# speedometer.net
KiCad netlist of a schematic drawn in EAGLE
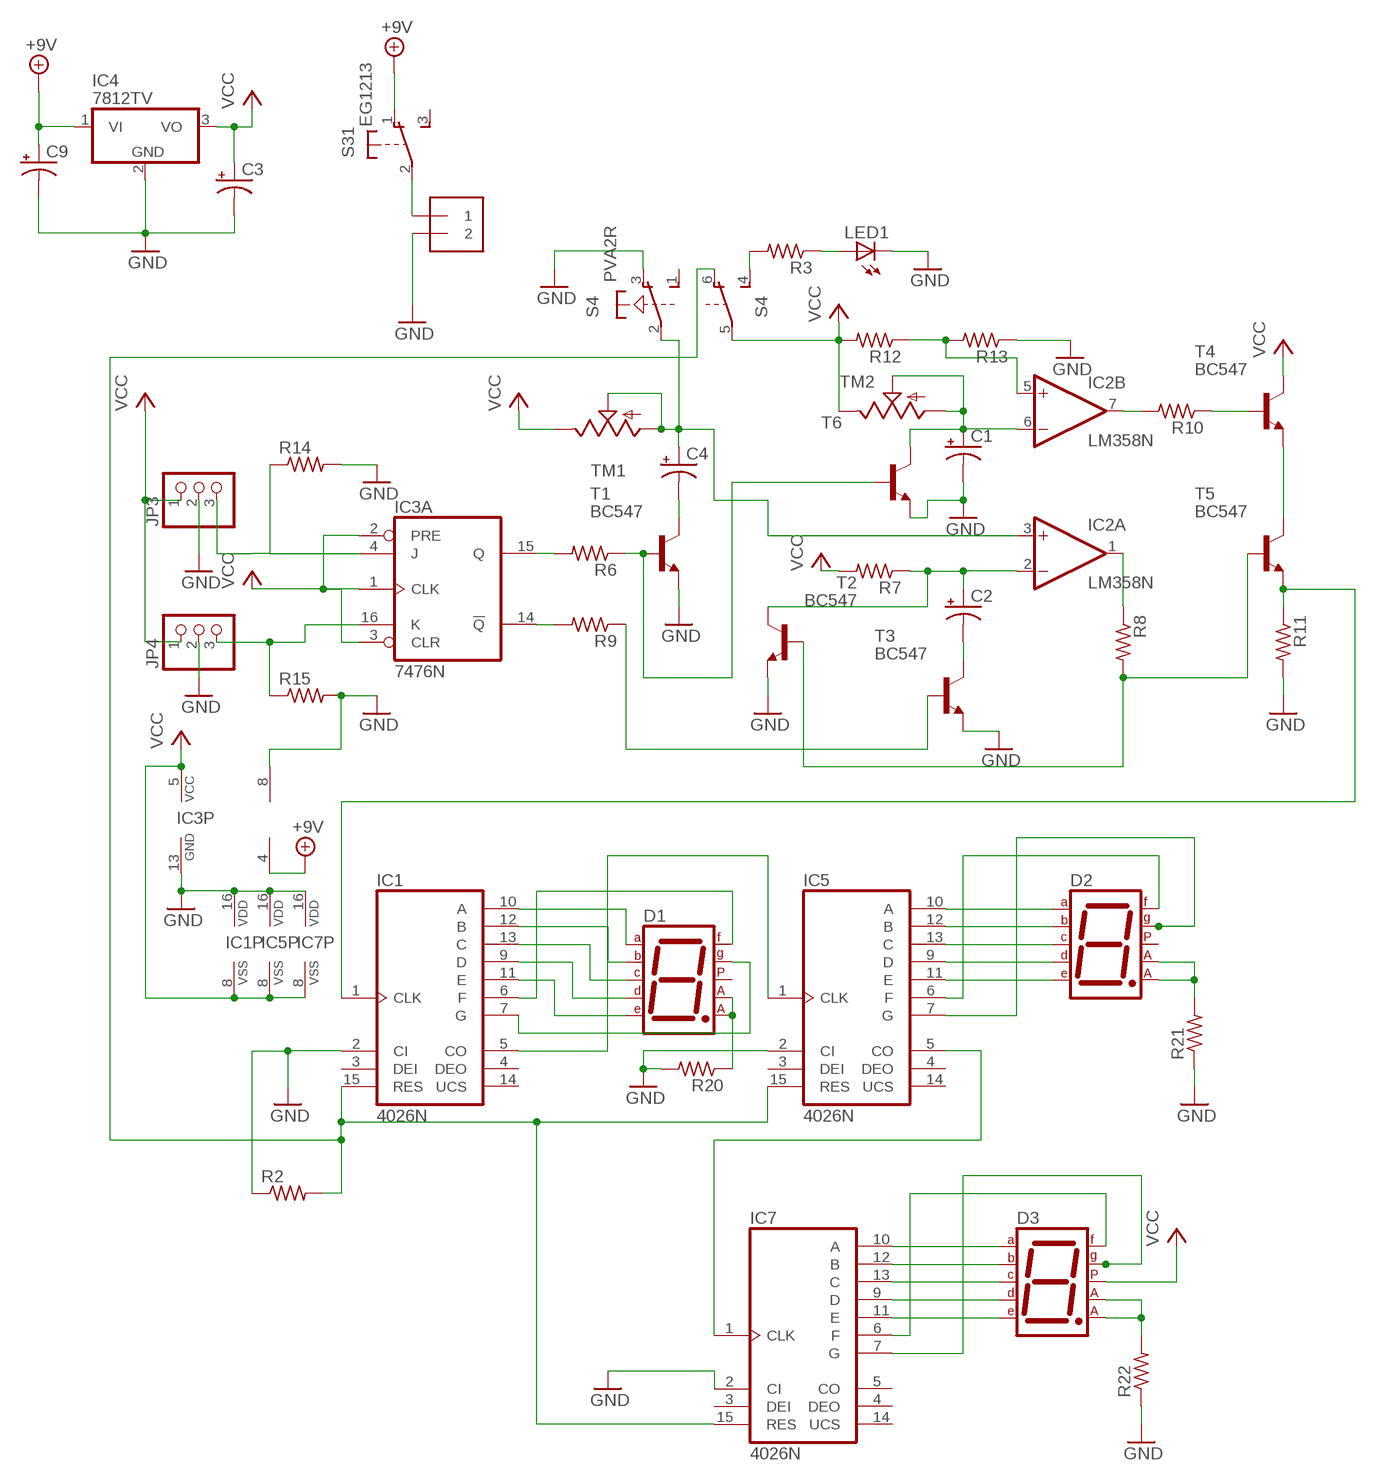
[diagram p0: schematic, sheet 1]

(export (version "E")
  (design (tool "Eeschema 10.0.6"))
  (components
    (comp (ref "C1")
      (value "CPOL-USE2-4")
      (footprint "eagle-import:E2-4")
      (libsource (lib "eagle-import") (part "CPOL-USE2-4"))
    )
    (comp (ref "C2")
      (value "CPOL-USE2-4")
      (footprint "eagle-import:E2-4")
      (libsource (lib "eagle-import") (part "CPOL-USE2-4"))
    )
    (comp (ref "C3")
      (value "CPOL-USE2-4")
      (footprint "eagle-import:E2-4")
      (libsource (lib "eagle-import") (part "CPOL-USE2-4"))
    )
    (comp (ref "C4")
      (value "CPOL-USE2-4")
      (footprint "eagle-import:E2-4")
      (libsource (lib "eagle-import") (part "CPOL-USE2-4"))
    )
    (comp (ref "C9")
      (value "CPOL-USE2.5-6")
      (footprint "eagle-import:E2,5-6")
      (libsource (lib "eagle-import") (part "CPOL-USE2.5-6"))
    )
    (comp (ref "D1")
      (value "7SEG-CA")
      (footprint "eagle-import:7SEG-13")
      (libsource (lib "eagle-import") (part "7SEG-CA"))
    )
    (comp (ref "D2")
      (value "7SEG-CA")
      (footprint "eagle-import:7SEG-13")
      (libsource (lib "eagle-import") (part "7SEG-CA"))
    )
    (comp (ref "D3")
      (value "7SEG-CA")
      (footprint "eagle-import:7SEG-13")
      (libsource (lib "eagle-import") (part "7SEG-CA"))
    )
    (comp (ref "IC1")
      (value "4026N")
      (footprint "eagle-import:DIL16")
      (libsource (lib "eagle-import") (part "4026N"))
    )
    (comp (ref "IC2")
      (value "LM358N")
      (footprint "eagle-import:DIL08")
      (libsource (lib "eagle-import") (part "LM358N"))
    )
    (comp (ref "IC3")
      (value "7476N")
      (footprint "eagle-import:DIL16")
      (libsource (lib "eagle-import") (part "7476N"))
    )
    (comp (ref "IC4")
      (value "7812TV")
      (footprint "eagle-import:TO220V")
      (libsource (lib "eagle-import") (part "78TV12"))
    )
    (comp (ref "IC5")
      (value "4026N")
      (footprint "eagle-import:DIL16")
      (libsource (lib "eagle-import") (part "4026N"))
    )
    (comp (ref "IC7")
      (value "4026N")
      (footprint "eagle-import:DIL16")
      (libsource (lib "eagle-import") (part "4026N"))
    )
    (comp (ref "J1")
      (value "1X2-3.5MM")
      (footprint "eagle-import:1X2-3.5MM")
      (libsource (lib "eagle-import") (part "1X2-3.5MM"))
    )
    (comp (ref "JP3")
      (value "PINHD-1X3")
      (footprint "eagle-import:1X03")
      (libsource (lib "eagle-import") (part "PINHD-1X3"))
    )
    (comp (ref "JP4")
      (value "PINHD-1X3")
      (footprint "eagle-import:1X03")
      (libsource (lib "eagle-import") (part "PINHD-1X3"))
    )
    (comp (ref "LED1")
      (value "LED5MM")
      (footprint "eagle-import:LED5MM")
      (libsource (lib "eagle-import") (part "LED5MM"))
    )
    (comp (ref "R2")
      (value "R-US_0204/7")
      (footprint "eagle-import:0204_7")
      (libsource (lib "eagle-import") (part "R-US_0204/7"))
    )
    (comp (ref "R3")
      (value "R-US_0204/7")
      (footprint "eagle-import:0204_7")
      (libsource (lib "eagle-import") (part "R-US_0204/7"))
    )
    (comp (ref "R6")
      (value "R-US_0204/7")
      (footprint "eagle-import:0204_7")
      (libsource (lib "eagle-import") (part "R-US_0204/7"))
    )
    (comp (ref "R7")
      (value "R-US_0204/7")
      (footprint "eagle-import:0204_7")
      (libsource (lib "eagle-import") (part "R-US_0204/7"))
    )
    (comp (ref "R8")
      (value "R-US_0204/7")
      (footprint "eagle-import:0204_7")
      (libsource (lib "eagle-import") (part "R-US_0204/7"))
    )
    (comp (ref "R9")
      (value "R-US_0204/7")
      (footprint "eagle-import:0204_7")
      (libsource (lib "eagle-import") (part "R-US_0204/7"))
    )
    (comp (ref "R10")
      (value "R-US_0204/7")
      (footprint "eagle-import:0204_7")
      (libsource (lib "eagle-import") (part "R-US_0204/7"))
    )
    (comp (ref "R11")
      (value "R-US_0204/7")
      (footprint "eagle-import:0204_7")
      (libsource (lib "eagle-import") (part "R-US_0204/7"))
    )
    (comp (ref "R12")
      (value "R-US_0204/7")
      (footprint "eagle-import:0204_7")
      (libsource (lib "eagle-import") (part "R-US_0204/7"))
    )
    (comp (ref "R13")
      (value "R-US_0204/7")
      (footprint "eagle-import:0204_7")
      (libsource (lib "eagle-import") (part "R-US_0204/7"))
    )
    (comp (ref "R14")
      (value "R-US_0204/7")
      (footprint "eagle-import:0204_7")
      (libsource (lib "eagle-import") (part "R-US_0204/7"))
    )
    (comp (ref "R15")
      (value "R-US_0204/7")
      (footprint "eagle-import:0204_7")
      (libsource (lib "eagle-import") (part "R-US_0204/7"))
    )
    (comp (ref "R20")
      (value "R-US_0204/7")
      (footprint "eagle-import:0204_7")
      (libsource (lib "eagle-import") (part "R-US_0204/7"))
    )
    (comp (ref "R21")
      (value "R-US_0204/7")
      (footprint "eagle-import:0204_7")
      (libsource (lib "eagle-import") (part "R-US_0204/7"))
    )
    (comp (ref "R22")
      (value "R-US_0204/7")
      (footprint "eagle-import:0204_7")
      (libsource (lib "eagle-import") (part "R-US_0204/7"))
    )
    (comp (ref "S3")
      (value "EG1213")
      (footprint "eagle-import:EG1213")
      (libsource (lib "eagle-import") (part "EG1213"))
    )
    (comp (ref "S4")
      (value "PVA2R")
      (footprint "eagle-import:PVA2R")
      (libsource (lib "eagle-import") (part "PVA2R"))
    )
    (comp (ref "T1")
      (value "BC547")
      (footprint "eagle-import:TO92")
      (libsource (lib "eagle-import") (part "BC547"))
    )
    (comp (ref "T2")
      (value "BC547")
      (footprint "eagle-import:TO92")
      (libsource (lib "eagle-import") (part "BC547"))
    )
    (comp (ref "T3")
      (value "BC547")
      (footprint "eagle-import:TO92")
      (libsource (lib "eagle-import") (part "BC547"))
    )
    (comp (ref "T4")
      (value "BC547")
      (footprint "eagle-import:TO92")
      (libsource (lib "eagle-import") (part "BC547"))
    )
    (comp (ref "T5")
      (value "BC547")
      (footprint "eagle-import:TO92")
      (libsource (lib "eagle-import") (part "BC547"))
    )
    (comp (ref "T6")
      (value "BC547")
      (footprint "eagle-import:TO92")
      (libsource (lib "eagle-import") (part "BC547"))
    )
    (comp (ref "TM1")
      (value "TRIM")
      (footprint "eagle-import:6MM")
      (libsource (lib "eagle-import") (part "TRIM"))
    )
    (comp (ref "TM2")
      (value "TRIM")
      (footprint "eagle-import:6MM")
      (libsource (lib "eagle-import") (part "TRIM"))
    )
  )
  (nets
    (net (code "1") (name "+9V") (class "Default")
      (node (ref "C9") (pin "+") (pinfunction "+_+") (pintype "passive"))
      (node (ref "IC2") (pin "4") (pinfunction "V-_4") (pintype "power_in"))
      (node (ref "IC4") (pin "1") (pinfunction "VI_1") (pintype "input"))
      (node (ref "S3") (pin "1") (pinfunction "O_1") (pintype "passive"))
    )
    (net (code "2") (name "GND") (class "Default")
      (node (ref "C1") (pin "-") (pinfunction "-_-") (pintype "passive"))
      (node (ref "C3") (pin "-") (pinfunction "-_-") (pintype "passive"))
      (node (ref "C9") (pin "-") (pinfunction "-_-") (pintype "passive"))
      (node (ref "IC1") (pin "16") (pinfunction "VDD_16") (pintype "power_in"))
      (node (ref "IC1") (pin "2") (pinfunction "CI_2") (pintype "input"))
      (node (ref "IC2") (pin "8") (pinfunction "V+_8") (pintype "power_in"))
      (node (ref "IC3") (pin "13") (pinfunction "GND_13") (pintype "power_in"))
      (node (ref "IC4") (pin "2") (pinfunction "GND_2") (pintype "passive"))
      (node (ref "IC5") (pin "16") (pinfunction "VDD_16") (pintype "power_in"))
      (node (ref "IC5") (pin "2") (pinfunction "CI_2") (pintype "input"))
      (node (ref "IC7") (pin "16") (pinfunction "VDD_16") (pintype "power_in"))
      (node (ref "IC7") (pin "2") (pinfunction "CI_2") (pintype "input"))
      (node (ref "J1") (pin "2") (pinfunction "2_2") (pintype "passive"))
      (node (ref "JP3") (pin "2") (pinfunction "2_2") (pintype "passive"))
      (node (ref "JP4") (pin "2") (pinfunction "2_2") (pintype "passive"))
      (node (ref "LED1") (pin "K") (pinfunction "C_K") (pintype "passive"))
      (node (ref "R11") (pin "2") (pinfunction "2_2") (pintype "passive"))
      (node (ref "R13") (pin "1") (pinfunction "1_1") (pintype "passive"))
      (node (ref "R14") (pin "2") (pinfunction "2_2") (pintype "passive"))
      (node (ref "R15") (pin "2") (pinfunction "2_2") (pintype "passive"))
      (node (ref "R2") (pin "1") (pinfunction "1_1") (pintype "passive"))
      (node (ref "R20") (pin "2") (pinfunction "2_2") (pintype "passive"))
      (node (ref "R21") (pin "1") (pinfunction "1_1") (pintype "passive"))
      (node (ref "R22") (pin "1") (pinfunction "1_1") (pintype "passive"))
      (node (ref "S4") (pin "3") (pinfunction "O_3") (pintype "passive"))
      (node (ref "T1") (pin "1") (pinfunction "E_1") (pintype "passive"))
      (node (ref "T2") (pin "1") (pinfunction "E_1") (pintype "passive"))
      (node (ref "T3") (pin "1") (pinfunction "E_1") (pintype "passive"))
      (node (ref "T6") (pin "1") (pinfunction "E_1") (pintype "passive"))
    )
    (net (code "3") (name "Net-(D1-A)") (class "Default")
      (node (ref "D1") (pin "7") (pinfunction "A_7") (pintype "passive"))
      (node (ref "IC1") (pin "10") (pinfunction "A_10") (pintype "output"))
    )
    (net (code "4") (name "Net-(D1-B)") (class "Default")
      (node (ref "D1") (pin "6") (pinfunction "B_6") (pintype "passive"))
      (node (ref "IC1") (pin "12") (pinfunction "B_12") (pintype "output"))
    )
    (net (code "5") (name "Net-(D1-C)") (class "Default")
      (node (ref "D1") (pin "4") (pinfunction "C_4") (pintype "passive"))
      (node (ref "IC1") (pin "13") (pinfunction "C_13") (pintype "output"))
    )
    (net (code "6") (name "Net-(D1-CA1)") (class "Default")
      (node (ref "D1") (pin "3") (pinfunction "CA1_3") (pintype "passive"))
      (node (ref "D1") (pin "8") (pinfunction "CA2_8") (pintype "passive"))
      (node (ref "R20") (pin "1") (pinfunction "1_1") (pintype "passive"))
    )
    (net (code "7") (name "Net-(D1-D)") (class "Default")
      (node (ref "D1") (pin "2") (pinfunction "D_2") (pintype "passive"))
      (node (ref "IC1") (pin "9") (pinfunction "D_9") (pintype "output"))
    )
    (net (code "8") (name "Net-(D1-E)") (class "Default")
      (node (ref "D1") (pin "1") (pinfunction "E_1") (pintype "passive"))
      (node (ref "IC1") (pin "11") (pinfunction "E_11") (pintype "output"))
    )
    (net (code "9") (name "Net-(D1-F)") (class "Default")
      (node (ref "D1") (pin "9") (pinfunction "F_9") (pintype "passive"))
      (node (ref "IC1") (pin "6") (pinfunction "F_6") (pintype "output"))
    )
    (net (code "10") (name "Net-(D1-G)") (class "Default")
      (node (ref "D1") (pin "10") (pinfunction "G_10") (pintype "passive"))
      (node (ref "IC1") (pin "7") (pinfunction "G_7") (pintype "output"))
    )
    (net (code "11") (name "Net-(D2-A)") (class "Default")
      (node (ref "D2") (pin "7") (pinfunction "A_7") (pintype "passive"))
      (node (ref "IC5") (pin "10") (pinfunction "A_10") (pintype "output"))
    )
    (net (code "12") (name "Net-(D2-B)") (class "Default")
      (node (ref "D2") (pin "6") (pinfunction "B_6") (pintype "passive"))
      (node (ref "IC5") (pin "12") (pinfunction "B_12") (pintype "output"))
    )
    (net (code "13") (name "Net-(D2-C)") (class "Default")
      (node (ref "D2") (pin "4") (pinfunction "C_4") (pintype "passive"))
      (node (ref "IC5") (pin "13") (pinfunction "C_13") (pintype "output"))
    )
    (net (code "14") (name "Net-(D2-CA1)") (class "Default")
      (node (ref "D2") (pin "3") (pinfunction "CA1_3") (pintype "passive"))
      (node (ref "D2") (pin "8") (pinfunction "CA2_8") (pintype "passive"))
      (node (ref "R21") (pin "2") (pinfunction "2_2") (pintype "passive"))
    )
    (net (code "15") (name "Net-(D2-D)") (class "Default")
      (node (ref "D2") (pin "2") (pinfunction "D_2") (pintype "passive"))
      (node (ref "IC5") (pin "9") (pinfunction "D_9") (pintype "output"))
    )
    (net (code "16") (name "Net-(D2-E)") (class "Default")
      (node (ref "D2") (pin "1") (pinfunction "E_1") (pintype "passive"))
      (node (ref "IC5") (pin "11") (pinfunction "E_11") (pintype "output"))
    )
    (net (code "17") (name "Net-(D2-F)") (class "Default")
      (node (ref "D2") (pin "9") (pinfunction "F_9") (pintype "passive"))
      (node (ref "IC5") (pin "6") (pinfunction "F_6") (pintype "output"))
    )
    (net (code "18") (name "Net-(D2-G)") (class "Default")
      (node (ref "D2") (pin "10") (pinfunction "G_10") (pintype "passive"))
      (node (ref "IC5") (pin "7") (pinfunction "G_7") (pintype "output"))
    )
    (net (code "19") (name "Net-(D3-A)") (class "Default")
      (node (ref "D3") (pin "7") (pinfunction "A_7") (pintype "passive"))
      (node (ref "IC7") (pin "10") (pinfunction "A_10") (pintype "output"))
    )
    (net (code "20") (name "Net-(D3-B)") (class "Default")
      (node (ref "D3") (pin "6") (pinfunction "B_6") (pintype "passive"))
      (node (ref "IC7") (pin "12") (pinfunction "B_12") (pintype "output"))
    )
    (net (code "21") (name "Net-(D3-C)") (class "Default")
      (node (ref "D3") (pin "4") (pinfunction "C_4") (pintype "passive"))
      (node (ref "IC7") (pin "13") (pinfunction "C_13") (pintype "output"))
    )
    (net (code "22") (name "Net-(D3-CA1)") (class "Default")
      (node (ref "D3") (pin "3") (pinfunction "CA1_3") (pintype "passive"))
      (node (ref "D3") (pin "8") (pinfunction "CA2_8") (pintype "passive"))
      (node (ref "R22") (pin "2") (pinfunction "2_2") (pintype "passive"))
    )
    (net (code "23") (name "Net-(D3-D)") (class "Default")
      (node (ref "D3") (pin "2") (pinfunction "D_2") (pintype "passive"))
      (node (ref "IC7") (pin "9") (pinfunction "D_9") (pintype "output"))
    )
    (net (code "24") (name "Net-(D3-E)") (class "Default")
      (node (ref "D3") (pin "1") (pinfunction "E_1") (pintype "passive"))
      (node (ref "IC7") (pin "11") (pinfunction "E_11") (pintype "output"))
    )
    (net (code "25") (name "Net-(D3-F)") (class "Default")
      (node (ref "D3") (pin "9") (pinfunction "F_9") (pintype "passive"))
      (node (ref "IC7") (pin "6") (pinfunction "F_6") (pintype "output"))
    )
    (net (code "26") (name "Net-(D3-G)") (class "Default")
      (node (ref "D3") (pin "10") (pinfunction "G_10") (pintype "passive"))
      (node (ref "IC7") (pin "7") (pinfunction "G_7") (pintype "output"))
    )
    (net (code "27") (name "Net-(IC1A-CLK)") (class "Default")
      (node (ref "IC1") (pin "1") (pinfunction "CLK_1") (pintype "input"))
      (node (ref "R11") (pin "1") (pinfunction "1_1") (pintype "passive"))
      (node (ref "T5") (pin "1") (pinfunction "E_1") (pintype "passive"))
    )
    (net (code "28") (name "Net-(IC1A-CO)") (class "Default")
      (node (ref "IC1") (pin "5") (pinfunction "CO_5") (pintype "output"))
      (node (ref "IC5") (pin "1") (pinfunction "CLK_1") (pintype "input"))
    )
    (net (code "29") (name "Net-(IC1A-RES)") (class "Default")
      (node (ref "IC1") (pin "15") (pinfunction "RES_15") (pintype "input"))
      (node (ref "IC5") (pin "15") (pinfunction "RES_15") (pintype "input"))
      (node (ref "IC7") (pin "15") (pinfunction "RES_15") (pintype "input"))
      (node (ref "R2") (pin "2") (pinfunction "2_2") (pintype "passive"))
      (node (ref "S4") (pin "6") (pinfunction "O_6") (pintype "passive"))
    )
    (net (code "30") (name "Net-(IC2A-+IN)") (class "Default")
      (node (ref "C4") (pin "+") (pinfunction "+_+") (pintype "passive"))
      (node (ref "IC2") (pin "3") (pinfunction "+IN_3") (pintype "input"))
      (node (ref "S4") (pin "2") (pinfunction "P_2") (pintype "passive"))
      (node (ref "TM1") (pin "A") (pinfunction "A_A") (pintype "passive"))
      (node (ref "TM1") (pin "S") (pinfunction "S_S") (pintype "passive"))
    )
    (net (code "31") (name "Net-(IC2A--IN)") (class "Default")
      (node (ref "C2") (pin "+") (pinfunction "+_+") (pintype "passive"))
      (node (ref "IC2") (pin "2") (pinfunction "-IN_2") (pintype "input"))
      (node (ref "R7") (pin "1") (pinfunction "1_1") (pintype "passive"))
      (node (ref "T2") (pin "3") (pinfunction "C_3") (pintype "passive"))
    )
    (net (code "32") (name "Net-(IC2A-OUT)") (class "Default")
      (node (ref "IC2") (pin "1") (pinfunction "OUT_1") (pintype "output"))
      (node (ref "R8") (pin "1") (pinfunction "1_1") (pintype "passive"))
    )
    (net (code "33") (name "Net-(IC2B-+IN)") (class "Default")
      (node (ref "IC2") (pin "5") (pinfunction "+IN_5") (pintype "input"))
      (node (ref "R12") (pin "1") (pinfunction "1_1") (pintype "passive"))
      (node (ref "R13") (pin "2") (pinfunction "2_2") (pintype "passive"))
    )
    (net (code "34") (name "Net-(IC2B--IN)") (class "Default")
      (node (ref "C1") (pin "+") (pinfunction "+_+") (pintype "passive"))
      (node (ref "IC2") (pin "6") (pinfunction "-IN_6") (pintype "input"))
      (node (ref "T6") (pin "3") (pinfunction "C_3") (pintype "passive"))
      (node (ref "TM2") (pin "A") (pinfunction "A_A") (pintype "passive"))
      (node (ref "TM2") (pin "S") (pinfunction "S_S") (pintype "passive"))
    )
    (net (code "35") (name "Net-(IC2B-OUT)") (class "Default")
      (node (ref "IC2") (pin "7") (pinfunction "OUT_7") (pintype "output"))
      (node (ref "R10") (pin "2") (pinfunction "2_2") (pintype "passive"))
    )
    (net (code "36") (name "Net-(IC3A-J)") (class "Default")
      (node (ref "IC3") (pin "4") (pinfunction "J_4") (pintype "input"))
      (node (ref "JP3") (pin "3") (pinfunction "3_3") (pintype "passive"))
      (node (ref "R14") (pin "1") (pinfunction "1_1") (pintype "passive"))
    )
    (net (code "37") (name "Net-(IC3A-K)") (class "Default")
      (node (ref "IC3") (pin "16") (pinfunction "K_16") (pintype "input"))
      (node (ref "JP4") (pin "3") (pinfunction "3_3") (pintype "passive"))
      (node (ref "R15") (pin "1") (pinfunction "1_1") (pintype "passive"))
    )
    (net (code "38") (name "Net-(IC3A-Q)") (class "Default")
      (node (ref "IC3") (pin "15") (pinfunction "Q_15") (pintype "output"))
      (node (ref "R6") (pin "2") (pinfunction "2_2") (pintype "passive"))
    )
    (net (code "39") (name "Net-(IC3A-~{Q})") (class "Default")
      (node (ref "IC3") (pin "14") (pinfunction "~{Q}_14") (pintype "output"))
      (node (ref "R9") (pin "2") (pinfunction "2_2") (pintype "passive"))
    )
    (net (code "40") (name "Net-(IC5A-CO)") (class "Default")
      (node (ref "IC5") (pin "5") (pinfunction "CO_5") (pintype "output"))
      (node (ref "IC7") (pin "1") (pinfunction "CLK_1") (pintype "input"))
    )
    (net (code "41") (name "Net-(LED1-PadA)") (class "Default")
      (node (ref "LED1") (pin "A") (pinfunction "A_A") (pintype "passive"))
      (node (ref "R3") (pin "1") (pinfunction "1_1") (pintype "passive"))
    )
    (net (code "42") (name "Net-(S3A-P)") (class "Default")
      (node (ref "J1") (pin "1") (pinfunction "1_1") (pintype "passive"))
      (node (ref "S3") (pin "2") (pinfunction "P_2") (pintype "passive"))
    )
    (net (code "43") (name "Net-(S4B-S)") (class "Default")
      (node (ref "R3") (pin "2") (pinfunction "2_2") (pintype "passive"))
      (node (ref "S4") (pin "4") (pinfunction "S_4") (pintype "passive"))
    )
    (net (code "44") (name "Net-(T1-B)") (class "Default")
      (node (ref "R6") (pin "1") (pinfunction "1_1") (pintype "passive"))
      (node (ref "T1") (pin "2") (pinfunction "B_2") (pintype "passive"))
      (node (ref "T6") (pin "2") (pinfunction "B_2") (pintype "passive"))
    )
    (net (code "45") (name "Net-(T1-C)") (class "Default")
      (node (ref "C4") (pin "-") (pinfunction "-_-") (pintype "passive"))
      (node (ref "T1") (pin "3") (pinfunction "C_3") (pintype "passive"))
    )
    (net (code "46") (name "Net-(T2-B)") (class "Default")
      (node (ref "R8") (pin "2") (pinfunction "2_2") (pintype "passive"))
      (node (ref "T2") (pin "2") (pinfunction "B_2") (pintype "passive"))
      (node (ref "T5") (pin "2") (pinfunction "B_2") (pintype "passive"))
    )
    (net (code "47") (name "Net-(T3-B)") (class "Default")
      (node (ref "R9") (pin "1") (pinfunction "1_1") (pintype "passive"))
      (node (ref "T3") (pin "2") (pinfunction "B_2") (pintype "passive"))
    )
    (net (code "48") (name "Net-(T3-C)") (class "Default")
      (node (ref "C2") (pin "-") (pinfunction "-_-") (pintype "passive"))
      (node (ref "T3") (pin "3") (pinfunction "C_3") (pintype "passive"))
    )
    (net (code "49") (name "Net-(T4-B)") (class "Default")
      (node (ref "R10") (pin "1") (pinfunction "1_1") (pintype "passive"))
      (node (ref "T4") (pin "2") (pinfunction "B_2") (pintype "passive"))
    )
    (net (code "50") (name "Net-(T4-E)") (class "Default")
      (node (ref "T4") (pin "1") (pinfunction "E_1") (pintype "passive"))
      (node (ref "T5") (pin "3") (pinfunction "C_3") (pintype "passive"))
    )
    (net (code "51") (name "VCC") (class "Default")
      (node (ref "C3") (pin "+") (pinfunction "+_+") (pintype "passive"))
      (node (ref "D3") (pin "5") (pinfunction "DP_5") (pintype "passive"))
      (node (ref "IC1") (pin "8") (pinfunction "VSS_8") (pintype "power_in"))
      (node (ref "IC3") (pin "1") (pinfunction "CLK_1") (pintype "input"))
      (node (ref "IC3") (pin "2") (pinfunction "PRE_2") (pintype "input"))
      (node (ref "IC3") (pin "3") (pinfunction "CLR_3") (pintype "input"))
      (node (ref "IC3") (pin "5") (pinfunction "VCC_5") (pintype "power_in"))
      (node (ref "IC4") (pin "3") (pinfunction "VO_3") (pintype "passive"))
      (node (ref "IC5") (pin "8") (pinfunction "VSS_8") (pintype "power_in"))
      (node (ref "IC7") (pin "8") (pinfunction "VSS_8") (pintype "power_in"))
      (node (ref "JP3") (pin "1") (pinfunction "1_1") (pintype "passive"))
      (node (ref "JP4") (pin "1") (pinfunction "1_1") (pintype "passive"))
      (node (ref "R12") (pin "2") (pinfunction "2_2") (pintype "passive"))
      (node (ref "R7") (pin "2") (pinfunction "2_2") (pintype "passive"))
      (node (ref "S4") (pin "5") (pinfunction "P_5") (pintype "passive"))
      (node (ref "T4") (pin "3") (pinfunction "C_3") (pintype "passive"))
      (node (ref "TM1") (pin "E") (pinfunction "E_E") (pintype "passive"))
      (node (ref "TM2") (pin "E") (pinfunction "E_E") (pintype "passive"))
    )
    (net (code "52") (name "unconnected-(D1-DP-Pad5)") (class "Default")
      (node (ref "D1") (pin "5") (pinfunction "DP_5") (pintype "passive"))
    )
    (net (code "53") (name "unconnected-(D2-DP-Pad5)") (class "Default")
      (node (ref "D2") (pin "5") (pinfunction "DP_5") (pintype "passive"))
    )
    (net (code "54") (name "unconnected-(IC1A-DEI-Pad3)") (class "Default")
      (node (ref "IC1") (pin "3") (pinfunction "DEI_3") (pintype "input"))
    )
    (net (code "55") (name "unconnected-(IC1A-DEO-Pad4)") (class "Default")
      (node (ref "IC1") (pin "4") (pinfunction "DEO_4") (pintype "output"))
    )
    (net (code "56") (name "unconnected-(IC1A-UCS-Pad14)") (class "Default")
      (node (ref "IC1") (pin "14") (pinfunction "UCS_14") (pintype "output"))
    )
    (net (code "57") (name "unconnected-(IC5A-DEI-Pad3)") (class "Default")
      (node (ref "IC5") (pin "3") (pinfunction "DEI_3") (pintype "input"))
    )
    (net (code "58") (name "unconnected-(IC5A-DEO-Pad4)") (class "Default")
      (node (ref "IC5") (pin "4") (pinfunction "DEO_4") (pintype "output"))
    )
    (net (code "59") (name "unconnected-(IC5A-UCS-Pad14)") (class "Default")
      (node (ref "IC5") (pin "14") (pinfunction "UCS_14") (pintype "output"))
    )
    (net (code "60") (name "unconnected-(IC7A-CO-Pad5)") (class "Default")
      (node (ref "IC7") (pin "5") (pinfunction "CO_5") (pintype "output"))
    )
    (net (code "61") (name "unconnected-(IC7A-DEI-Pad3)") (class "Default")
      (node (ref "IC7") (pin "3") (pinfunction "DEI_3") (pintype "input"))
    )
    (net (code "62") (name "unconnected-(IC7A-DEO-Pad4)") (class "Default")
      (node (ref "IC7") (pin "4") (pinfunction "DEO_4") (pintype "output"))
    )
    (net (code "63") (name "unconnected-(IC7A-UCS-Pad14)") (class "Default")
      (node (ref "IC7") (pin "14") (pinfunction "UCS_14") (pintype "output"))
    )
    (net (code "64") (name "unconnected-(S3A-S-Pad3)") (class "Default")
      (node (ref "S3") (pin "3") (pinfunction "S_3") (pintype "passive"))
    )
    (net (code "65") (name "unconnected-(S4A-S-Pad1)") (class "Default")
      (node (ref "S4") (pin "1") (pinfunction "S_1") (pintype "passive"))
    )
  )
)
